# yard-ice-toplevel.net
KiCad netlist of a schematic drawn in Altium Designer
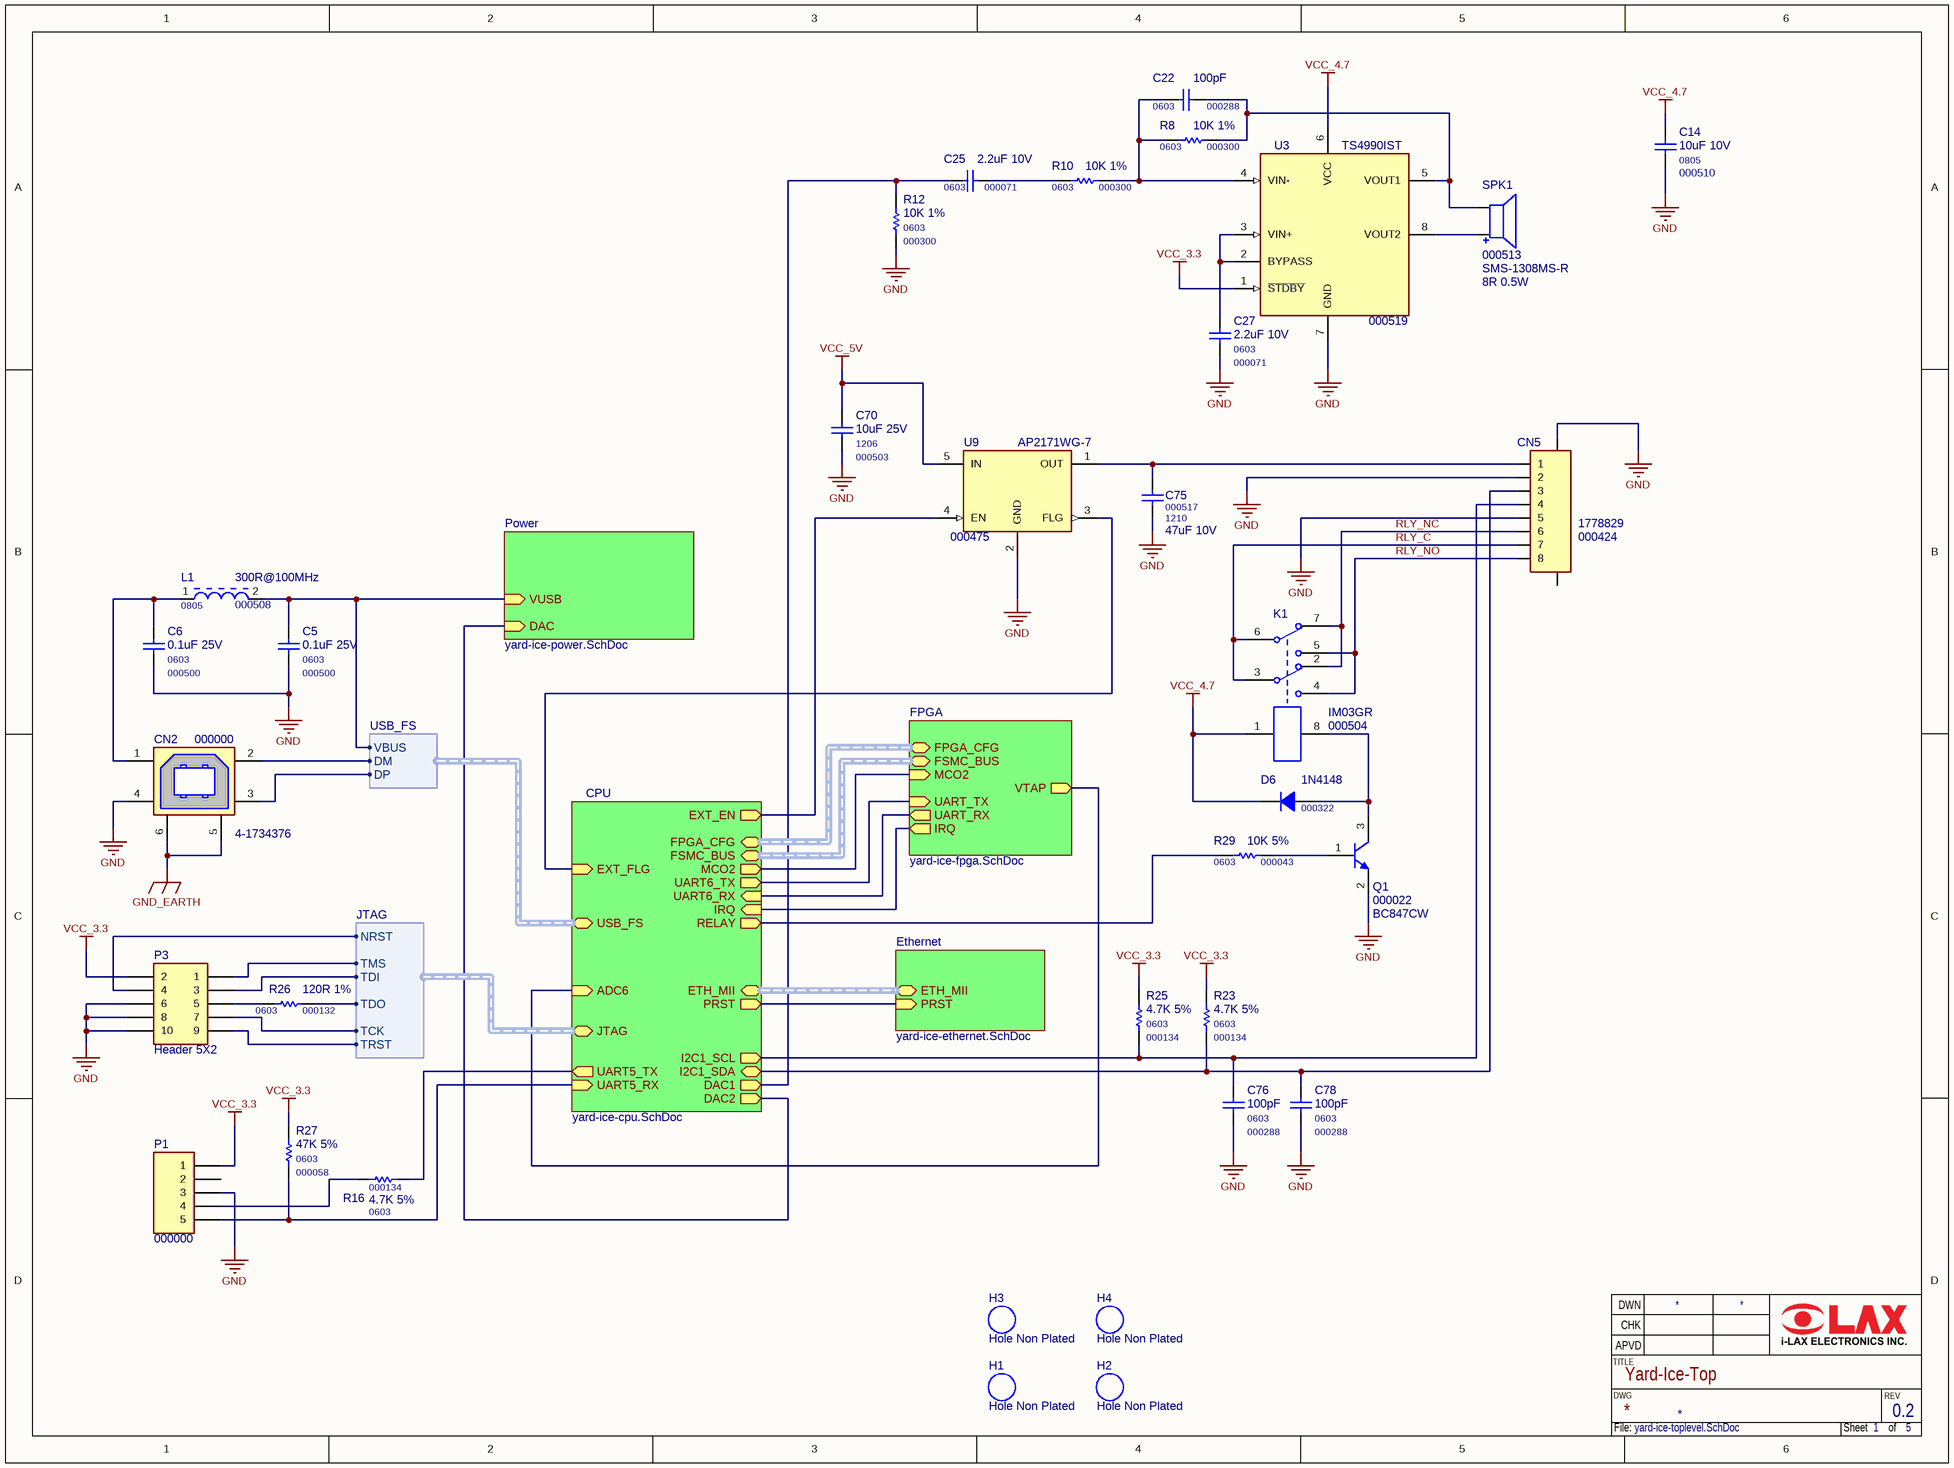
[diagram p0: yard-ice-toplevel.SchDoc]

(export (version "E")
  (design (tool "Eeschema 10.0.6"))
  (components
    (comp (ref "C5")
      (value "000500")
      (footprint "C0603M")
      (description "SMD Ceramic Chip Capacitor - 0603 - X7R")
      (fields
        (field (name "ALTIUM_VALUE") "0.1uF 25V")
        (field (name "PACKAGE") "0603")
        (field (name "MF") "TDK")
      )
      (libsource (lib "discrete-sm") (part "C0603"))
    )
    (comp (ref "C6")
      (value "000500")
      (footprint "C0603M")
      (description "SMD Ceramic Chip Capacitor - 0603 - X7R")
      (fields
        (field (name "ALTIUM_VALUE") "0.1uF 25V")
        (field (name "PACKAGE") "0603")
        (field (name "MF") "TDK")
      )
      (libsource (lib "discrete-sm") (part "C0603"))
    )
    (comp (ref "C14")
      (value "000510")
      (footprint "C0805M")
      (description "SMD Ceramic Chip Capacitor - 0805 - X7R")
      (fields
        (field (name "ALTIUM_VALUE") "10uF 10V")
        (field (name "PACKAGE") "0805")
        (field (name "MF") "TDK")
      )
      (libsource (lib "sm_cap") (part "C0805"))
    )
    (comp (ref "C22")
      (value "000288")
      (footprint "C0603M")
      (description "SMD Ceramic Chip Capacitor - 0603")
      (fields (field (name "ALTIUM_VALUE") "100pF") (field (name "PACKAGE") "0603"))
      (libsource (lib "discrete-sm") (part "C0603"))
    )
    (comp (ref "C25")
      (value "000071")
      (footprint "C0603M")
      (description "SMD Ceramic Chip Capacitor - 0603 - X7R")
      (fields
        (field (name "ALTIUM_VALUE") "2.2uF 10V")
        (field (name "PACKAGE") "0603")
        (field (name "MF") "Taiyo Yuden")
      )
      (libsource (lib "discrete-sm") (part "C0603"))
    )
    (comp (ref "C27")
      (value "000071")
      (footprint "C0603M")
      (description "SMD Ceramic Chip Capacitor - 0603 - X7R")
      (fields
        (field (name "ALTIUM_VALUE") "2.2uF 10V")
        (field (name "PACKAGE") "0603")
        (field (name "MF") "Taiyo Yuden")
      )
      (libsource (lib "discrete-sm") (part "C0603"))
    )
    (comp (ref "C70")
      (value "000503")
      (footprint "C1206M")
      (description "SMD Ceramic Chip Capacitor - 1206 - X7R")
      (fields
        (field (name "ALTIUM_VALUE") "10uF 25V")
        (field (name "PACKAGE") "1206")
        (field (name "MF") "Taiyo Yuden")
      )
      (libsource (lib "discrete-sm") (part "C1206"))
    )
    (comp (ref "C75")
      (value "000517")
      (footprint "C1210M")
      (description "SMD Ceramic Chip Capacitor - 1210 - X7R")
      (fields
        (field (name "PACKAGE") "1210")
        (field (name "ALTIUM_VALUE") "47uF 10V")
        (field (name "MF") "Taiyo Yuden")
      )
      (libsource (lib "discrete-sm") (part "C12010"))
    )
    (comp (ref "C76")
      (value "000288")
      (footprint "C0603M")
      (description "SMD Ceramic Chip Capacitor - 0603")
      (fields (field (name "ALTIUM_VALUE") "100pF") (field (name "PACKAGE") "0603"))
      (libsource (lib "discrete-sm") (part "C0603"))
    )
    (comp (ref "C78")
      (value "000288")
      (footprint "C0603M")
      (description "SMD Ceramic Chip Capacitor - 0603")
      (fields (field (name "ALTIUM_VALUE") "100pF") (field (name "PACKAGE") "0603"))
      (libsource (lib "discrete-sm") (part "C0603"))
    )
    (comp (ref "CN2")
      (value "000000")
      (footprint "4-1734376")
      (description "USB Type B - Right Angle - Thru Hole")
      (fields (field (name "ALTIUM_VALUE") "4-1734376") (field (name "MF") "Tyco"))
      (libsource (lib "tyco-conn") (part "4-1734376"))
    )
    (comp (ref "CN5")
      (value "000424")
      (footprint "1778829")
      (description "Terminal Block, Header, 8-Pos")
      (fields (field (name "ALTIUM_VALUE") "1778829") (field (name "MF") "Phoenix Contacts"))
      (libsource (lib "phoenix-contact") (part "Combicon SMT 8"))
    )
    (comp (ref "D6")
      (value "000322")
      (footprint "SOD-123")
      (description "Schottky Barrier Diode")
      (fields (field (name "MF") "Diodes Inc") (field (name "ALTIUM_VALUE") "1N4148"))
      (libsource (lib "diodes-inc") (part "1N4148W"))
    )
    (comp (ref "H1")
      (value "Hole Non Plated")
      (footprint "Hole NP 3.2x5.0x5.0")
      (libsource (lib "mechanical") (part "Hole Non Plated"))
    )
    (comp (ref "H2")
      (value "Hole Non Plated")
      (footprint "Hole NP 3.2x5.0x5.0")
      (libsource (lib "mechanical") (part "Hole Non Plated"))
    )
    (comp (ref "H3")
      (value "Hole Non Plated")
      (footprint "Hole NP 3.2x5.0x5.0")
      (libsource (lib "mechanical") (part "Hole Non Plated"))
    )
    (comp (ref "H4")
      (value "Hole Non Plated")
      (footprint "Hole NP 3.2x5.0x5.0")
      (libsource (lib "mechanical") (part "Hole Non Plated"))
    )
    (comp (ref "K1")
      (value "000504")
      (footprint "Relay-10X6")
      (description "Dual-Pole Dual-Throw Relay")
      (fields (field (name "ALTIUM_VALUE") "IM03GR") (field (name "MF") "Tyco"))
      (libsource (lib "sm-electromechanical") (part "Relay-DPDT"))
    )
    (comp (ref "L1")
      (value "000508")
      (footprint "L0805M")
      (description "SMD Chip Inductor - 0805")
      (fields
        (field (name "ALTIUM_VALUE") "300R@100MHz")
        (field (name "PACKAGE") "0805")
        (field (name "MF") "TDK")
      )
      (libsource (lib "discrete-sm") (part "L0805"))
    )
    (comp (ref "P1")
      (value "000000")
      (footprint "TSW-105-07-G-S")
      (description "Header, 5-Pin")
      (libsource (lib "samtec-board-to-board") (part "Header 5"))
    )
    (comp (ref "P3")
      (value "Header 5X2")
      (footprint "TSW-105-07-G-D")
      (description "Header 5-Pin, Dual row")
      (libsource (lib "samtec-board-to-board") (part "Header 5X2"))
    )
    (comp (ref "Q1")
      (value "000022")
      (footprint "SOT-323")
      (description "NPN General-purpose Transistor")
      (fields (field (name "ALTIUM_VALUE") "BC847CW") (field (name "MF") "Diodes Inc"))
      (libsource (lib "diodes-inc") (part "BC847CW"))
    )
    (comp (ref "R8")
      (value "000300")
      (footprint "R0603M")
      (description "SMD Chip Resistor - 0603")
      (fields (field (name "ALTIUM_VALUE") "10K 1%") (field (name "PACKAGE") "0603"))
      (libsource (lib "discrete-sm") (part "R0603"))
    )
    (comp (ref "R10")
      (value "000300")
      (footprint "R0603M")
      (description "SMD Chip Resistor - 0603")
      (fields (field (name "ALTIUM_VALUE") "10K 1%") (field (name "PACKAGE") "0603"))
      (libsource (lib "discrete-sm") (part "R0603"))
    )
    (comp (ref "R12")
      (value "000300")
      (footprint "R0603M")
      (description "SMD Chip Resistor - 0603")
      (fields (field (name "ALTIUM_VALUE") "10K 1%") (field (name "PACKAGE") "0603"))
      (libsource (lib "discrete-sm") (part "R0603"))
    )
    (comp (ref "R16")
      (value "000134")
      (footprint "R0603M")
      (description "SMD Chip Resistor - 0603")
      (fields (field (name "ALTIUM_VALUE") "4.7K 5%") (field (name "PACKAGE") "0603"))
      (libsource (lib "discrete-sm") (part "R0603"))
    )
    (comp (ref "R23")
      (value "000134")
      (footprint "R0603M")
      (description "SMD Chip Resistor - 0603")
      (fields (field (name "ALTIUM_VALUE") "4.7K 5%") (field (name "PACKAGE") "0603"))
      (libsource (lib "discrete-sm") (part "R0603"))
    )
    (comp (ref "R25")
      (value "000134")
      (footprint "R0603M")
      (description "SMD Chip Resistor - 0603")
      (fields (field (name "ALTIUM_VALUE") "4.7K 5%") (field (name "PACKAGE") "0603"))
      (libsource (lib "discrete-sm") (part "R0603"))
    )
    (comp (ref "R26")
      (value "000132")
      (footprint "R0603M")
      (description "SMD Chip Resistor - 0603")
      (fields (field (name "ALTIUM_VALUE") "120R 1%") (field (name "PACKAGE") "0603"))
      (libsource (lib "discrete-sm") (part "R0603"))
    )
    (comp (ref "R27")
      (value "000058")
      (footprint "R0603M")
      (description "SMD Chip Resistor - 0603")
      (fields (field (name "ALTIUM_VALUE") "47K 5%") (field (name "PACKAGE") "0603"))
      (libsource (lib "discrete-sm") (part "R0603"))
    )
    (comp (ref "R29")
      (value "000043")
      (footprint "R0603M")
      (description "SMD Chip Resistor - 0603")
      (fields (field (name "ALTIUM_VALUE") "10K 5%") (field (name "PACKAGE") "0603"))
      (libsource (lib "discrete-sm") (part "R0603"))
    )
    (comp (ref "SPK1")
      (value "000513")
      (footprint "SMS-1308MS-R")
      (description "Loudspeaker")
      (fields
        (field (name "MF") "PUI-Audio")
        (field (name "MF PN") "SMS-1308MS-R")
        (field (name "ALTIUM_VALUE") "8R 0.5W")
      )
      (libsource (lib "pui-audio") (part "SMS-1308MS-R"))
    )
    (comp (ref "U3")
      (value "000519")
      (footprint "MiniSO-8M")
      (description "1.2 W audio power amplifier with active-low standby mode")
      (fields (field (name "ALTIUM_VALUE") "TS4990IST"))
      (libsource (lib "st-audio") (part "TS4990IST"))
    )
    (comp (ref "U9")
      (value "000475")
      (footprint "SOT-25")
      (description "1A SINGLE CHANNEL CURRENT-LIMITED POWER  SWITCH")
      (fields (field (name "ALTIUM_VALUE") "AP2171WG-7") (field (name "MF") "Diodes Inc"))
      (libsource (lib "diodes-inc-pwr-mgmt") (part "AP2171W"))
    )
  )
  (nets
    (net (code "3") (name "/DAC1") (class "Default")
      (node (ref "C25") (pin "1") (pinfunction "1_1") (pintype "passive"))
      (node (ref "R12") (pin "2") (pinfunction "2_2") (pintype "passive"))
    )
    (net (code "6") (name "/EXT_EN") (class "Default")
      (node (ref "U9") (pin "4") (pinfunction "EN_4") (pintype "input"))
    )
    (net (code "7") (name "/EXT_FLG") (class "Default")
      (node (ref "U9") (pin "3") (pinfunction "FLG_3") (pintype "output"))
    )
    (net (code "10") (name "/I2C1_SCL") (class "Default")
      (node (ref "C76") (pin "1") (pinfunction "1_1") (pintype "passive"))
      (node (ref "CN5") (pin "4") (pinfunction "4_4") (pintype "passive"))
      (node (ref "R25") (pin "1") (pinfunction "1_1") (pintype "passive"))
    )
    (net (code "11") (name "/I2C1_SDA") (class "Default")
      (node (ref "C78") (pin "1") (pinfunction "1_1") (pintype "passive"))
      (node (ref "CN5") (pin "3") (pinfunction "3_3") (pintype "passive"))
      (node (ref "R23") (pin "1") (pinfunction "1_1") (pintype "passive"))
    )
    (net (code "15") (name "/RELAY") (class "Default")
      (node (ref "R29") (pin "2") (pinfunction "2_2") (pintype "passive"))
    )
    (net (code "16") (name "/RLY_C") (class "Default")
      (node (ref "CN5") (pin "7") (pinfunction "7_7") (pintype "passive"))
      (node (ref "K1") (pin "3") (pinfunction "3_3") (pintype "passive"))
      (node (ref "K1") (pin "6") (pinfunction "6_6") (pintype "passive"))
    )
    (net (code "17") (name "/RLY_NC") (class "Default")
      (node (ref "CN5") (pin "6") (pinfunction "6_6") (pintype "passive"))
      (node (ref "K1") (pin "2") (pinfunction "2_2") (pintype "passive"))
      (node (ref "K1") (pin "7") (pinfunction "7_7") (pintype "passive"))
    )
    (net (code "18") (name "/RLY_NO") (class "Default")
      (node (ref "CN5") (pin "8") (pinfunction "8_8") (pintype "passive"))
      (node (ref "K1") (pin "4") (pinfunction "4_4") (pintype "passive"))
      (node (ref "K1") (pin "5") (pinfunction "5_5") (pintype "passive"))
    )
    (net (code "19") (name "/UART5_RX") (class "Default")
      (node (ref "P1") (pin "5") (pinfunction "5_5") (pintype "passive"))
      (node (ref "R27") (pin "1") (pinfunction "1_1") (pintype "passive"))
    )
    (net (code "20") (name "/UART5_TX") (class "Default")
      (node (ref "R16") (pin "1") (pinfunction "1_1") (pintype "passive"))
    )
    (net (code "24") (name "/VUSB") (class "Default")
      (node (ref "C5") (pin "1") (pinfunction "1_1") (pintype "passive"))
      (node (ref "L1") (pin "2") (pinfunction "2_2") (pintype "passive"))
    )
    (net (code "27") (name "GND") (class "Default")
      (node (ref "C14") (pin "2") (pinfunction "2_2") (pintype "passive"))
      (node (ref "C27") (pin "2") (pinfunction "2_2") (pintype "passive"))
      (node (ref "C5") (pin "2") (pinfunction "2_2") (pintype "passive"))
      (node (ref "C6") (pin "2") (pinfunction "2_2") (pintype "passive"))
      (node (ref "C70") (pin "2") (pinfunction "2_2") (pintype "passive"))
      (node (ref "C75") (pin "2") (pinfunction "2_2") (pintype "passive"))
      (node (ref "C76") (pin "2") (pinfunction "2_2") (pintype "passive"))
      (node (ref "C78") (pin "2") (pinfunction "2_2") (pintype "passive"))
      (node (ref "CN2") (pin "4") (pinfunction "4_4") (pintype "passive"))
      (node (ref "CN5") (pin "2") (pinfunction "2_2") (pintype "passive"))
      (node (ref "CN5") (pin "5") (pinfunction "5_5") (pintype "passive"))
      (node (ref "CN5") (pin "9") (pinfunction "9_9") (pintype "passive"))
      (node (ref "P1") (pin "3") (pinfunction "3_3") (pintype "passive"))
      (node (ref "P3") (pin "10") (pinfunction "10_10") (pintype "passive"))
      (node (ref "P3") (pin "6") (pinfunction "6_6") (pintype "passive"))
      (node (ref "P3") (pin "8") (pinfunction "8_8") (pintype "passive"))
      (node (ref "Q1") (pin "2") (pinfunction "E_2") (pintype "passive"))
      (node (ref "R12") (pin "1") (pinfunction "1_1") (pintype "passive"))
      (node (ref "U3") (pin "7") (pinfunction "GND_7") (pintype "power_in"))
      (node (ref "U9") (pin "2") (pinfunction "GND_2") (pintype "power_in"))
    )
    (net (code "28") (name "GND_EARTH") (class "Default")
      (node (ref "CN2") (pin "5") (pinfunction "SHIELD_5") (pintype "passive"))
      (node (ref "CN2") (pin "6") (pinfunction "SHIELD_6") (pintype "passive"))
    )
    (net (code "29") (name "Net-(C6-Pad1)") (class "Default")
      (node (ref "C6") (pin "1") (pinfunction "1_1") (pintype "passive"))
      (node (ref "CN2") (pin "1") (pinfunction "1_1") (pintype "passive"))
      (node (ref "L1") (pin "1") (pinfunction "1_1") (pintype "passive"))
    )
    (net (code "30") (name "Net-(C25-Pad2)") (class "Default")
      (node (ref "C25") (pin "2") (pinfunction "2_2") (pintype "passive"))
      (node (ref "R10") (pin "2") (pinfunction "2_2") (pintype "passive"))
    )
    (net (code "31") (name "Net-(D6-A)") (class "Default")
      (node (ref "D6") (pin "1") (pinfunction "A_1") (pintype "passive"))
      (node (ref "K1") (pin "8") (pinfunction "8_8") (pintype "passive"))
      (node (ref "Q1") (pin "3") (pinfunction "C_3") (pintype "passive"))
    )
    (net (code "32") (name "Net-(P1-Pad4)") (class "Default")
      (node (ref "P1") (pin "4") (pinfunction "4_4") (pintype "passive"))
      (node (ref "R16") (pin "2") (pinfunction "2_2") (pintype "passive"))
    )
    (net (code "33") (name "Net-(P3-Pad5)") (class "Default")
      (node (ref "P3") (pin "5") (pinfunction "5_5") (pintype "passive"))
      (node (ref "R26") (pin "1") (pinfunction "1_1") (pintype "passive"))
    )
    (net (code "34") (name "Net-(Q1-B)") (class "Default")
      (node (ref "Q1") (pin "1") (pinfunction "B_1") (pintype "passive"))
      (node (ref "R29") (pin "1") (pinfunction "1_1") (pintype "passive"))
    )
    (net (code "35") (name "Net-(U3-BYPASS)") (class "Default")
      (node (ref "C27") (pin "1") (pinfunction "1_1") (pintype "passive"))
      (node (ref "U3") (pin "2") (pinfunction "BYPASS_2") (pintype "passive"))
      (node (ref "U3") (pin "3") (pinfunction "VIN+_3") (pintype "input"))
    )
    (net (code "36") (name "Net-(U3-VIN-)") (class "Default")
      (node (ref "C22") (pin "1") (pinfunction "1_1") (pintype "passive"))
      (node (ref "R10") (pin "1") (pinfunction "1_1") (pintype "passive"))
      (node (ref "R8") (pin "2") (pinfunction "2_2") (pintype "passive"))
      (node (ref "U3") (pin "4") (pinfunction "VIN-_4") (pintype "input"))
    )
    (net (code "37") (name "Net-(U3-VOUT1)") (class "Default")
      (node (ref "C22") (pin "2") (pinfunction "2_2") (pintype "passive"))
      (node (ref "R8") (pin "1") (pinfunction "1_1") (pintype "passive"))
      (node (ref "SPK1") (pin "2") (pinfunction "2_2") (pintype "passive"))
      (node (ref "U3") (pin "5") (pinfunction "VOUT1_5") (pintype "passive"))
    )
    (net (code "38") (name "Net-(U3-VOUT2)") (class "Default")
      (node (ref "SPK1") (pin "1") (pinfunction "1_1") (pintype "passive"))
      (node (ref "U3") (pin "8") (pinfunction "VOUT2_8") (pintype "passive"))
    )
    (net (code "39") (name "Net-(U9-OUT)") (class "Default")
      (node (ref "C75") (pin "1") (pinfunction "1_1") (pintype "passive"))
      (node (ref "CN5") (pin "1") (pinfunction "1_1") (pintype "passive"))
      (node (ref "U9") (pin "1") (pinfunction "OUT_1") (pintype "power_in"))
    )
    (net (code "40") (name "VCC_3.3") (class "Default")
      (node (ref "P1") (pin "1") (pinfunction "1_1") (pintype "passive"))
      (node (ref "P3") (pin "2") (pinfunction "2_2") (pintype "passive"))
      (node (ref "R23") (pin "2") (pinfunction "2_2") (pintype "passive"))
      (node (ref "R25") (pin "2") (pinfunction "2_2") (pintype "passive"))
      (node (ref "R27") (pin "2") (pinfunction "2_2") (pintype "passive"))
      (node (ref "U3") (pin "1") (pinfunction "~{STDBY}_1") (pintype "input"))
    )
    (net (code "41") (name "VCC_4.7") (class "Default")
      (node (ref "C14") (pin "1") (pinfunction "1_1") (pintype "passive"))
      (node (ref "D6") (pin "2") (pinfunction "K_2") (pintype "passive"))
      (node (ref "K1") (pin "1") (pinfunction "1_1") (pintype "passive"))
      (node (ref "U3") (pin "6") (pinfunction "VCC_6") (pintype "power_in"))
    )
    (net (code "42") (name "VCC_5V") (class "Default")
      (node (ref "C70") (pin "1") (pinfunction "1_1") (pintype "passive"))
      (node (ref "U9") (pin "5") (pinfunction "IN_5") (pintype "power_in"))
    )
    (net (code "43") (name "unconnected-(CN2-Pad2)") (class "Default")
      (node (ref "CN2") (pin "2") (pinfunction "2_2") (pintype "passive"))
    )
    (net (code "44") (name "unconnected-(CN2-Pad3)") (class "Default")
      (node (ref "CN2") (pin "3") (pinfunction "3_3") (pintype "passive"))
    )
    (net (code "45") (name "unconnected-(CN5-Pad10)") (class "Default")
      (node (ref "CN5") (pin "10") (pinfunction "10_10") (pintype "passive"))
    )
    (net (code "46") (name "unconnected-(P1-Pad2)") (class "Default")
      (node (ref "P1") (pin "2") (pinfunction "2_2") (pintype "passive"))
    )
    (net (code "47") (name "unconnected-(P3-Pad1)") (class "Default")
      (node (ref "P3") (pin "1") (pinfunction "1_1") (pintype "passive"))
    )
    (net (code "48") (name "unconnected-(P3-Pad3)") (class "Default")
      (node (ref "P3") (pin "3") (pinfunction "3_3") (pintype "passive"))
    )
    (net (code "49") (name "unconnected-(P3-Pad4)") (class "Default")
      (node (ref "P3") (pin "4") (pinfunction "4_4") (pintype "passive"))
    )
    (net (code "50") (name "unconnected-(P3-Pad7)") (class "Default")
      (node (ref "P3") (pin "7") (pinfunction "7_7") (pintype "passive"))
    )
    (net (code "51") (name "unconnected-(P3-Pad9)") (class "Default")
      (node (ref "P3") (pin "9") (pinfunction "9_9") (pintype "passive"))
    )
    (net (code "52") (name "unconnected-(R26-Pad2)") (class "Default")
      (node (ref "R26") (pin "2") (pinfunction "2_2") (pintype "passive"))
    )
  )
)
